# Con_vga_db15.net
KiCad netlist of a schematic drawn in Altium Designer
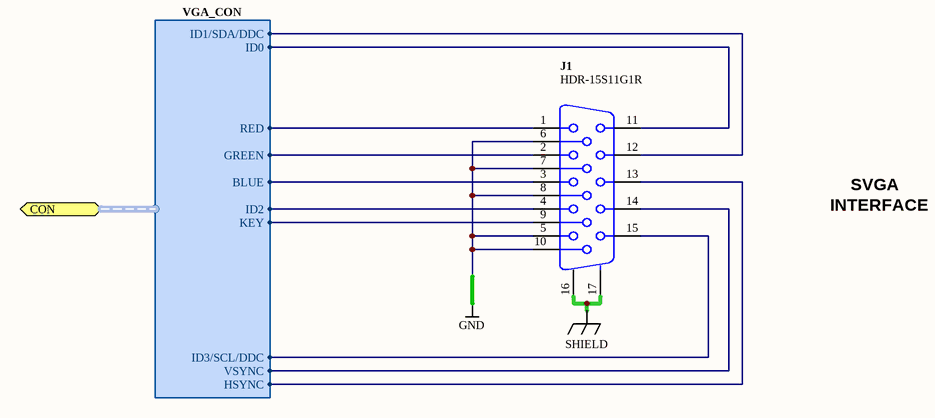
[diagram p0: Con_vga_db15.schdoc]

(export (version "E")
  (design (tool "Eeschema 10.0.6"))
  (components
    (comp (ref "J1")
      (value "HDR-15S11G1R")
      (footprint "DB15-VGA-Female")
      (description "Socket, High-Density DB15 (HD15) R/A Female Through-hole")
      (libsource (lib "AltiumDesignLibrary") (part "CON-DB-15-F-RA"))
    )
  )
  (nets
    (net (code "2") (name "/BLUE") (class "Default")
      (node (ref "J1") (pin "3") (pinfunction "3_3") (pintype "passive"))
    )
    (net (code "3") (name "/GREEN") (class "Default")
      (node (ref "J1") (pin "2") (pinfunction "2_2") (pintype "passive"))
    )
    (net (code "4") (name "/HSYNC") (class "Default")
      (node (ref "J1") (pin "13") (pinfunction "13_13") (pintype "passive"))
    )
    (net (code "5") (name "/ID0") (class "Default")
      (node (ref "J1") (pin "11") (pinfunction "11_11") (pintype "power_in"))
    )
    (net (code "6") (name "/ID1{slash}SDA{slash}DDC") (class "Default")
      (node (ref "J1") (pin "12") (pinfunction "12_12") (pintype "passive"))
    )
    (net (code "7") (name "/ID2") (class "Default")
      (node (ref "J1") (pin "4") (pinfunction "4_4") (pintype "passive"))
    )
    (net (code "8") (name "/ID3{slash}SCL{slash}DDC") (class "Default")
      (node (ref "J1") (pin "15") (pinfunction "15_15") (pintype "passive"))
    )
    (net (code "9") (name "/KEY") (class "Default")
      (node (ref "J1") (pin "9") (pinfunction "9_9") (pintype "passive"))
    )
    (net (code "10") (name "/RED") (class "Default")
      (node (ref "J1") (pin "1") (pinfunction "1_1") (pintype "passive"))
    )
    (net (code "11") (name "/VSYNC") (class "Default")
      (node (ref "J1") (pin "14") (pinfunction "14_14") (pintype "passive"))
    )
    (net (code "13") (name "GND") (class "Default")
      (node (ref "J1") (pin "10") (pinfunction "10_10") (pintype "power_in"))
      (node (ref "J1") (pin "5") (pinfunction "5_5") (pintype "power_in"))
      (node (ref "J1") (pin "6") (pinfunction "6_6") (pintype "power_in"))
      (node (ref "J1") (pin "7") (pinfunction "7_7") (pintype "power_in"))
      (node (ref "J1") (pin "8") (pinfunction "8_8") (pintype "power_in"))
    )
    (net (code "14") (name "SHIELD") (class "Default")
      (node (ref "J1") (pin "16") (pinfunction "MH1_16") (pintype "passive"))
      (node (ref "J1") (pin "17") (pinfunction "MH2_17") (pintype "passive"))
    )
  )
)
